# Temp_Sensor_B.net
KiCad netlist of a schematic drawn in EAGLE
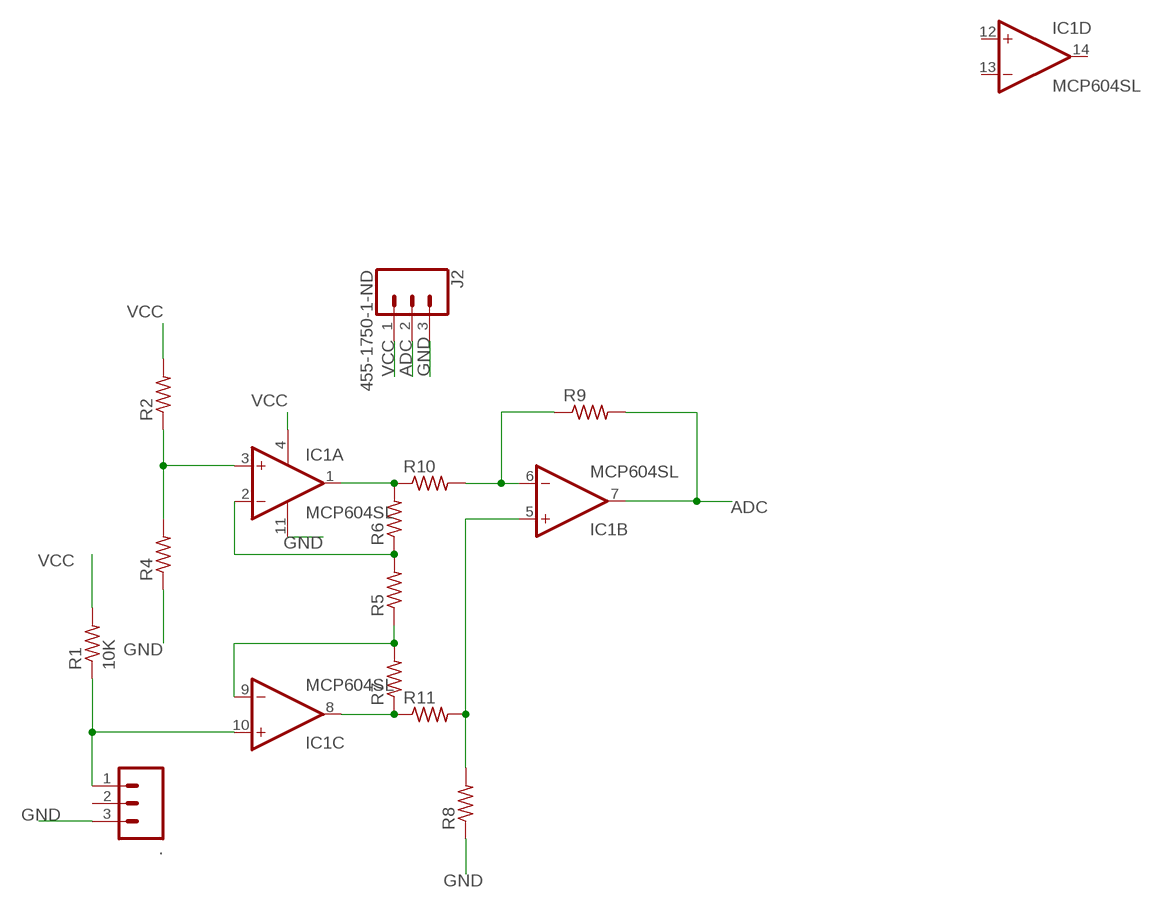
[diagram p0: schematic, sheet 1]

(export (version "E")
  (design (tool "Eeschema 10.0.6"))
  (components
    (comp (ref ".")
      (value "CONN_03SCREW_LOCK")
      (footprint "eagle-import:SCREWTERMINAL-3.5MM-3_LOCK.007S")
      (libsource (lib "eagle-import") (part "CONN_03SCREW_LOCK"))
    )
    (comp (ref "IC1")
      (value "MCP604SL")
      (footprint "eagle-import:SO14")
      (libsource (lib "eagle-import") (part "MCP604SL"))
    )
    (comp (ref "J2")
      (value "455-1750-1-ND")
      (footprint "eagle-import:1X03")
      (libsource (lib "eagle-import") (part "CONN_03"))
    )
    (comp (ref "R1")
      (value "10K")
      (footprint "eagle-import:R0603")
      (libsource (lib "eagle-import") (part "R-US_R0603"))
    )
    (comp (ref "R2")
      (value "R-US_R0603")
      (footprint "eagle-import:R0603")
      (libsource (lib "eagle-import") (part "R-US_R0603"))
    )
    (comp (ref "R4")
      (value "R-US_R0603")
      (footprint "eagle-import:R0603")
      (libsource (lib "eagle-import") (part "R-US_R0603"))
    )
    (comp (ref "R5")
      (value "R-US_R0603")
      (footprint "eagle-import:R0603")
      (libsource (lib "eagle-import") (part "R-US_R0603"))
    )
    (comp (ref "R6")
      (value "R-US_R0603")
      (footprint "eagle-import:R0603")
      (libsource (lib "eagle-import") (part "R-US_R0603"))
    )
    (comp (ref "R7")
      (value "R-US_R0603")
      (footprint "eagle-import:R0603")
      (libsource (lib "eagle-import") (part "R-US_R0603"))
    )
    (comp (ref "R8")
      (value "R-US_R0603")
      (footprint "eagle-import:R0603")
      (libsource (lib "eagle-import") (part "R-US_R0603"))
    )
    (comp (ref "R9")
      (value "R-US_R0603")
      (footprint "eagle-import:R0603")
      (libsource (lib "eagle-import") (part "R-US_R0603"))
    )
    (comp (ref "R10")
      (value "R-US_R0603")
      (footprint "eagle-import:R0603")
      (libsource (lib "eagle-import") (part "R-US_R0603"))
    )
    (comp (ref "R11")
      (value "R-US_R0603")
      (footprint "eagle-import:R0603")
      (libsource (lib "eagle-import") (part "R-US_R0603"))
    )
  )
  (nets
    (net (code "1") (name "/ADC") (class "Default")
      (node (ref "IC1") (pin "7") (pinfunction "OUT_7") (pintype "output"))
      (node (ref "J2") (pin "2") (pinfunction "2_2") (pintype "passive"))
      (node (ref "R9") (pin "2") (pinfunction "2_2") (pintype "passive"))
    )
    (net (code "2") (name "/GND") (class "Default")
      (node (ref ".") (pin "3") (pinfunction "3_3") (pintype "passive"))
      (node (ref "IC1") (pin "11") (pinfunction "V-_11") (pintype "power_in"))
      (node (ref "J2") (pin "3") (pinfunction "3_3") (pintype "passive"))
      (node (ref "R4") (pin "1") (pinfunction "1_1") (pintype "passive"))
      (node (ref "R8") (pin "1") (pinfunction "1_1") (pintype "passive"))
    )
    (net (code "3") (name "/VCC") (class "Default")
      (node (ref "IC1") (pin "4") (pinfunction "V+_4") (pintype "power_in"))
      (node (ref "J2") (pin "1") (pinfunction "1_1") (pintype "passive"))
      (node (ref "R1") (pin "2") (pinfunction "2_2") (pintype "passive"))
      (node (ref "R2") (pin "2") (pinfunction "2_2") (pintype "passive"))
    )
    (net (code "4") (name "Net-(IC1A-+IN)") (class "Default")
      (node (ref "IC1") (pin "3") (pinfunction "+IN_3") (pintype "input"))
      (node (ref "R2") (pin "1") (pinfunction "1_1") (pintype "passive"))
      (node (ref "R4") (pin "2") (pinfunction "2_2") (pintype "passive"))
    )
    (net (code "5") (name "Net-(IC1A--IN)") (class "Default")
      (node (ref "IC1") (pin "2") (pinfunction "-IN_2") (pintype "input"))
      (node (ref "R5") (pin "2") (pinfunction "2_2") (pintype "passive"))
      (node (ref "R6") (pin "1") (pinfunction "1_1") (pintype "passive"))
    )
    (net (code "6") (name "Net-(IC1A-OUT)") (class "Default")
      (node (ref "IC1") (pin "1") (pinfunction "OUT_1") (pintype "output"))
      (node (ref "R10") (pin "1") (pinfunction "1_1") (pintype "passive"))
      (node (ref "R6") (pin "2") (pinfunction "2_2") (pintype "passive"))
    )
    (net (code "7") (name "Net-(IC1B-+IN)") (class "Default")
      (node (ref "IC1") (pin "5") (pinfunction "+IN_5") (pintype "input"))
      (node (ref "R11") (pin "2") (pinfunction "2_2") (pintype "passive"))
      (node (ref "R8") (pin "2") (pinfunction "2_2") (pintype "passive"))
    )
    (net (code "8") (name "Net-(IC1B--IN)") (class "Default")
      (node (ref "IC1") (pin "6") (pinfunction "-IN_6") (pintype "input"))
      (node (ref "R10") (pin "2") (pinfunction "2_2") (pintype "passive"))
      (node (ref "R9") (pin "1") (pinfunction "1_1") (pintype "passive"))
    )
    (net (code "9") (name "Net-(IC1C-+IN)") (class "Default")
      (node (ref ".") (pin "1") (pinfunction "1_1") (pintype "passive"))
      (node (ref "IC1") (pin "10") (pinfunction "+IN_10") (pintype "input"))
      (node (ref "R1") (pin "1") (pinfunction "1_1") (pintype "passive"))
    )
    (net (code "10") (name "Net-(IC1C--IN)") (class "Default")
      (node (ref "IC1") (pin "9") (pinfunction "-IN_9") (pintype "input"))
      (node (ref "R5") (pin "1") (pinfunction "1_1") (pintype "passive"))
      (node (ref "R7") (pin "2") (pinfunction "2_2") (pintype "passive"))
    )
    (net (code "11") (name "Net-(IC1C-OUT)") (class "Default")
      (node (ref "IC1") (pin "8") (pinfunction "OUT_8") (pintype "output"))
      (node (ref "R11") (pin "1") (pinfunction "1_1") (pintype "passive"))
      (node (ref "R7") (pin "1") (pinfunction "1_1") (pintype "passive"))
    )
    (net (code "12") (name "unconnected-(.-Pad2)") (class "Default")
      (node (ref ".") (pin "2") (pinfunction "2_2") (pintype "passive"))
    )
    (net (code "13") (name "unconnected-(IC1D-+IN-Pad12)") (class "Default")
      (node (ref "IC1") (pin "12") (pinfunction "+IN_12") (pintype "input"))
    )
    (net (code "14") (name "unconnected-(IC1D--IN-Pad13)") (class "Default")
      (node (ref "IC1") (pin "13") (pinfunction "-IN_13") (pintype "input"))
    )
    (net (code "15") (name "unconnected-(IC1D-OUT-Pad14)") (class "Default")
      (node (ref "IC1") (pin "14") (pinfunction "OUT_14") (pintype "output"))
    )
  )
)
